# RAM_Bus.net
KiCad netlist of a schematic drawn in Altium Designer
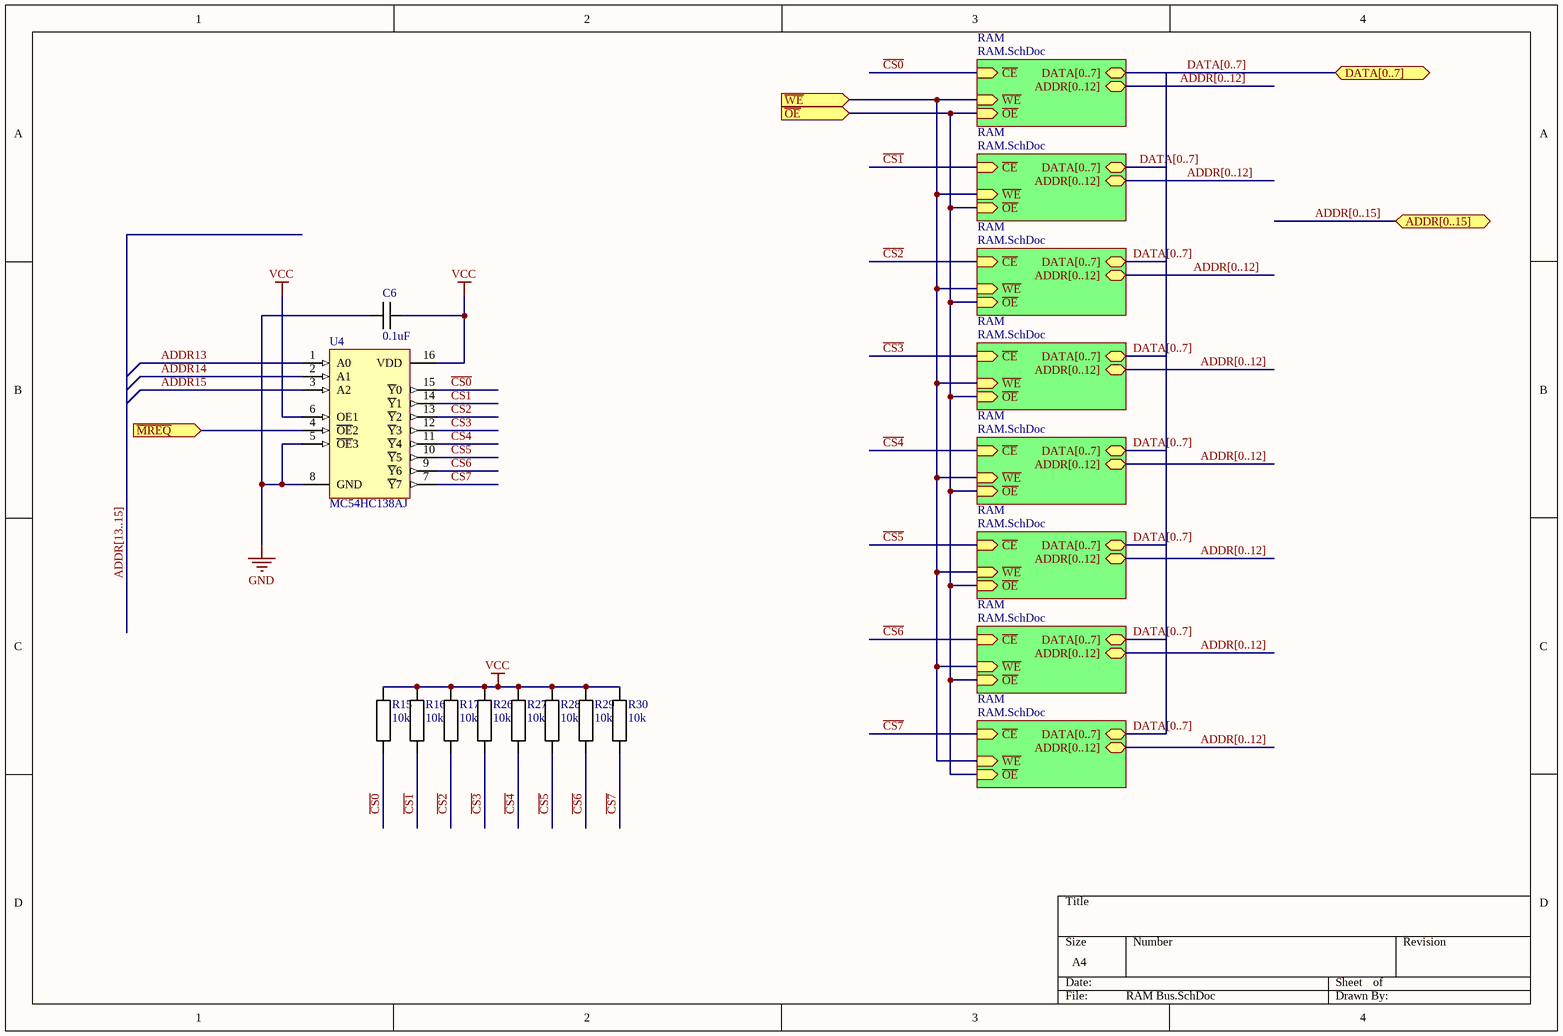
[diagram p0: RAM Bus.SchDoc]

(export (version "E")
  (design (tool "Eeschema 10.0.6"))
  (components
    (comp (ref "C6") (value "0.1uF") (footprint "SMD 0603") (libsource (lib "Maks_lib") (part "Capasitor")))
    (comp (ref "R15") (value "10k") (footprint "SMD 0603") (libsource (lib "Maks_lib") (part "Resistor")))
    (comp (ref "R16") (value "10k") (footprint "SMD 0603") (libsource (lib "Maks_lib") (part "Resistor")))
    (comp (ref "R17") (value "10k") (footprint "SMD 0603") (libsource (lib "Maks_lib") (part "Resistor")))
    (comp (ref "R26") (value "10k") (footprint "SMD 0603") (libsource (lib "Maks_lib") (part "Resistor")))
    (comp (ref "R27") (value "10k") (footprint "SMD 0603") (libsource (lib "Maks_lib") (part "Resistor")))
    (comp (ref "R28") (value "10k") (footprint "SMD 0603") (libsource (lib "Maks_lib") (part "Resistor")))
    (comp (ref "R29") (value "10k") (footprint "SMD 0603") (libsource (lib "Maks_lib") (part "Resistor")))
    (comp (ref "R30") (value "10k") (footprint "SMD 0603") (libsource (lib "Maks_lib") (part "Resistor")))
    (comp (ref "U4")
      (value "MC54HC138AJ")
      (footprint "620-09")
      (description "1-of-8 Decoder/Demultiplexer")
      (fields (field (name "PUBLISHER") "Altium Limited"))
      (libsource (lib "Motorola Logic Decoder Demux") (part "MC54HC138AJ"))
    )
  )
  (nets
    (net (code "22") (name "/ADDR13") (class "Default")
      (node (ref "U4") (pin "1") (pinfunction "A0_1") (pintype "input"))
    )
    (net (code "23") (name "/ADDR14") (class "Default")
      (node (ref "U4") (pin "2") (pinfunction "A1_2") (pintype "input"))
    )
    (net (code "24") (name "/ADDR15") (class "Default")
      (node (ref "U4") (pin "3") (pinfunction "A2_3") (pintype "input"))
    )
    (net (code "28") (name "/CS0") (class "Default")
      (node (ref "R15") (pin "1") (pinfunction "1_1") (pintype "passive"))
      (node (ref "U4") (pin "15") (pinfunction "~{Y}0_15") (pintype "output"))
    )
    (net (code "29") (name "/CS1") (class "Default")
      (node (ref "R16") (pin "1") (pinfunction "1_1") (pintype "passive"))
      (node (ref "U4") (pin "14") (pinfunction "~{Y}1_14") (pintype "output"))
    )
    (net (code "30") (name "/CS2") (class "Default")
      (node (ref "R17") (pin "1") (pinfunction "1_1") (pintype "passive"))
      (node (ref "U4") (pin "13") (pinfunction "~{Y}2_13") (pintype "output"))
    )
    (net (code "31") (name "/CS3") (class "Default")
      (node (ref "R26") (pin "1") (pinfunction "1_1") (pintype "passive"))
      (node (ref "U4") (pin "12") (pinfunction "~{Y}3_12") (pintype "output"))
    )
    (net (code "32") (name "/CS4") (class "Default")
      (node (ref "R27") (pin "1") (pinfunction "1_1") (pintype "passive"))
      (node (ref "U4") (pin "11") (pinfunction "~{Y}4_11") (pintype "output"))
    )
    (net (code "33") (name "/CS5") (class "Default")
      (node (ref "R28") (pin "1") (pinfunction "1_1") (pintype "passive"))
      (node (ref "U4") (pin "10") (pinfunction "~{Y}5_10") (pintype "output"))
    )
    (net (code "34") (name "/CS6") (class "Default")
      (node (ref "R29") (pin "1") (pinfunction "1_1") (pintype "passive"))
      (node (ref "U4") (pin "9") (pinfunction "~{Y}6_9") (pintype "output"))
    )
    (net (code "35") (name "/CS7") (class "Default")
      (node (ref "R30") (pin "1") (pinfunction "1_1") (pintype "passive"))
      (node (ref "U4") (pin "7") (pinfunction "~{Y}7_7") (pintype "output"))
    )
    (net (code "37") (name "/MREQ") (class "Default")
      (node (ref "U4") (pin "4") (pinfunction "~{OE}2_4") (pintype "input"))
    )
    (net (code "40") (name "GND") (class "Default")
      (node (ref "C6") (pin "1") (pinfunction "1_1") (pintype "passive"))
      (node (ref "U4") (pin "5") (pinfunction "~{OE}3_5") (pintype "input"))
      (node (ref "U4") (pin "8") (pinfunction "GND_8") (pintype "power_in"))
    )
    (net (code "41") (name "VCC") (class "Default")
      (node (ref "C6") (pin "2") (pinfunction "2_2") (pintype "passive"))
      (node (ref "R15") (pin "2") (pinfunction "2_2") (pintype "passive"))
      (node (ref "R16") (pin "2") (pinfunction "2_2") (pintype "passive"))
      (node (ref "R17") (pin "2") (pinfunction "2_2") (pintype "passive"))
      (node (ref "R26") (pin "2") (pinfunction "2_2") (pintype "passive"))
      (node (ref "R27") (pin "2") (pinfunction "2_2") (pintype "passive"))
      (node (ref "R28") (pin "2") (pinfunction "2_2") (pintype "passive"))
      (node (ref "R29") (pin "2") (pinfunction "2_2") (pintype "passive"))
      (node (ref "R30") (pin "2") (pinfunction "2_2") (pintype "passive"))
      (node (ref "U4") (pin "16") (pinfunction "VDD_16") (pintype "power_in"))
      (node (ref "U4") (pin "6") (pinfunction "OE1_6") (pintype "input"))
    )
  )
)
